# design.net
KiCad netlist of a schematic drawn in Altium Designer
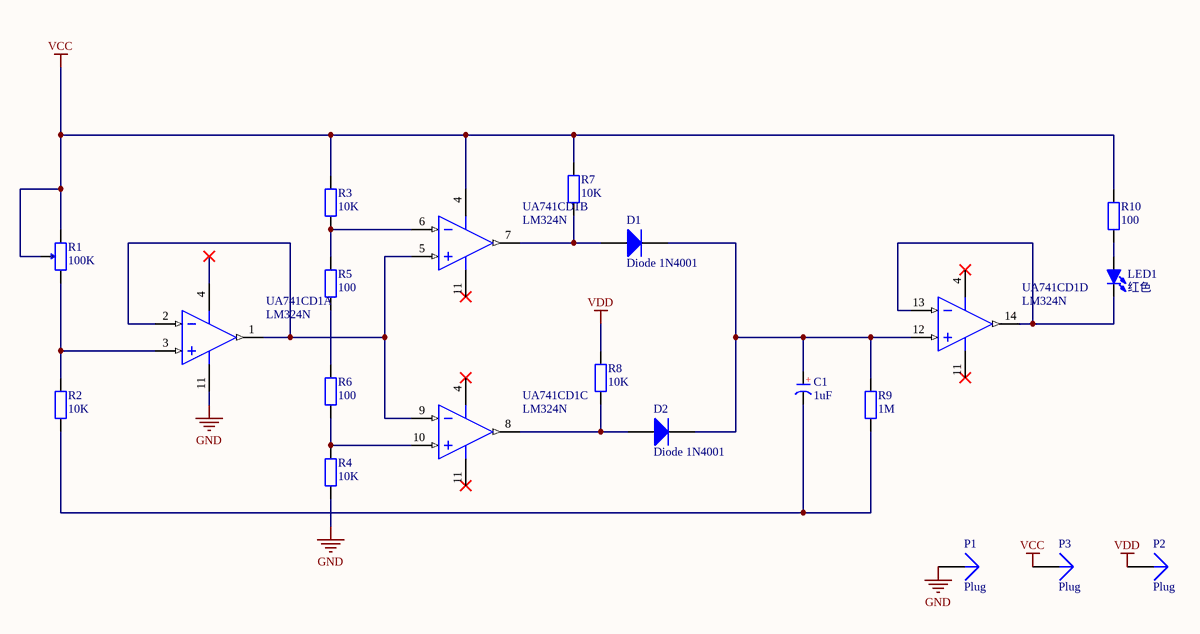
[diagram p0: 模电.SchDoc]

(export (version "E")
  (design (tool "Eeschema 10.0.6"))
  (components
    (comp (ref "C1")
      (value "1uF")
      (footprint "CAP 1.5*4*8")
      (description "直插电解电容")
      (libsource (lib "0.1 - 电阻-电容-电感") (part "C-CAP"))
    )
    (comp (ref "D1")
      (value "Diode 1N4001")
      (footprint "DO-41")
      (description "1 Amp General Purpose Rectifier")
      (fields (field (name "PUBLISHER") "Altium Limited"))
      (libsource (lib "Miscellaneous Devices") (part "Diode 1N4001"))
    )
    (comp (ref "D2")
      (value "Diode 1N4001")
      (footprint "DO-41")
      (description "1 Amp General Purpose Rectifier")
      (fields (field (name "PUBLISHER") "Altium Limited"))
      (libsource (lib "Miscellaneous Devices") (part "Diode 1N4001"))
    )
    (comp (ref "LED1")
      (value "红色")
      (footprint "LED 3MM-B")
      (description "插件LED")
      (libsource (lib "0.3 - LED") (part "LED-3MM"))
    )
    (comp (ref "P1")
      (value "Plug")
      (footprint "PIN1")
      (fields (field (name "PUBLISHER") "Altium Limited"))
      (libsource (lib "Miscellaneous Connectors") (part "Plug"))
    )
    (comp (ref "P2")
      (value "Plug")
      (footprint "PIN1")
      (fields (field (name "PUBLISHER") "Altium Limited"))
      (libsource (lib "Miscellaneous Connectors") (part "Plug"))
    )
    (comp (ref "P3")
      (value "Plug")
      (footprint "PIN1")
      (fields (field (name "PUBLISHER") "Altium Limited"))
      (libsource (lib "Miscellaneous Connectors") (part "Plug"))
    )
    (comp (ref "R1")
      (value "100K")
      (footprint "3362P")
      (description "贴片电位器")
      (libsource (lib "PCB_Project1") (part "RP-SMD"))
    )
    (comp (ref "R2")
      (value "10K")
      (footprint "RS 1/4W")
      (description "直插色环电阻")
      (libsource (lib "PCB_Project1") (part "R-CRR"))
    )
    (comp (ref "R3")
      (value "10K")
      (footprint "RS 1/4W")
      (description "直插色环电阻")
      (libsource (lib "PCB_Project1") (part "R-CRR"))
    )
    (comp (ref "R4")
      (value "10K")
      (footprint "RS 1/4W")
      (description "直插色环电阻")
      (libsource (lib "PCB_Project1") (part "R-CRR"))
    )
    (comp (ref "R5")
      (value "100")
      (footprint "RS 1/4W")
      (description "直插色环电阻")
      (libsource (lib "PCB_Project1") (part "R-CRR"))
    )
    (comp (ref "R6")
      (value "100")
      (footprint "RS 1/4W")
      (description "直插色环电阻")
      (libsource (lib "PCB_Project1") (part "R-CRR"))
    )
    (comp (ref "R7")
      (value "10K")
      (footprint "RS 1/4W")
      (description "直插色环电阻")
      (libsource (lib "PCB_Project1") (part "R-CRR"))
    )
    (comp (ref "R8")
      (value "10K")
      (footprint "RS 1/4W")
      (description "直插色环电阻")
      (libsource (lib "PCB_Project1") (part "R-CRR"))
    )
    (comp (ref "R9")
      (value "1M")
      (footprint "RS 1/4W")
      (description "直插色环电阻")
      (libsource (lib "PCB_Project1") (part "R-CRR"))
    )
    (comp (ref "R10")
      (value "100")
      (footprint "RS 1/4W")
      (description "直插色环电阻")
      (libsource (lib "PCB_Project1") (part "R-CRR"))
    )
    (comp (ref "UA741CD1")
      (value "LM324N")
      (footprint "DIP14")
      (description "Low Power Quad Operational Amplifier, 14-pin MDIP")
      (fields
        (field (name "MANUFACTURER") "National Semiconductor")
        (field (name "PUBLISHER") "Altium Limited")
      )
      (libsource (lib "Sheet1") (part "LM324N"))
    )
  )
  (nets
    (net (code "1") (name "GND") (class "Default")
      (node (ref "P1") (pin "1") (pinfunction "1_1") (pintype "passive"))
      (node (ref "R4") (pin "1") (pinfunction "1_1") (pintype "passive"))
      (node (ref "UA741CD1") (pin "11") (pinfunction "GND_11") (pintype "power_in"))
    )
    (net (code "2") (name "Net-(C1-A)") (class "Default")
      (node (ref "C1") (pin "1") (pinfunction "A_1") (pintype "passive"))
      (node (ref "D1") (pin "2") (pinfunction "K_2") (pintype "passive"))
      (node (ref "D2") (pin "2") (pinfunction "K_2") (pintype "passive"))
      (node (ref "R9") (pin "2") (pinfunction "2_2") (pintype "passive"))
      (node (ref "UA741CD1") (pin "12") (pinfunction "IN4+_12") (pintype "input"))
    )
    (net (code "3") (name "Net-(C1-K)") (class "Default")
      (node (ref "C1") (pin "2") (pinfunction "K_2") (pintype "passive"))
      (node (ref "R2") (pin "1") (pinfunction "1_1") (pintype "passive"))
      (node (ref "R9") (pin "1") (pinfunction "1_1") (pintype "passive"))
    )
    (net (code "4") (name "Net-(D1-A)") (class "Default")
      (node (ref "D1") (pin "1") (pinfunction "A_1") (pintype "passive"))
      (node (ref "R7") (pin "1") (pinfunction "1_1") (pintype "passive"))
      (node (ref "UA741CD1") (pin "7") (pinfunction "OUT2_7") (pintype "output"))
    )
    (net (code "5") (name "Net-(D2-A)") (class "Default")
      (node (ref "D2") (pin "1") (pinfunction "A_1") (pintype "passive"))
      (node (ref "R8") (pin "1") (pinfunction "1_1") (pintype "passive"))
      (node (ref "UA741CD1") (pin "8") (pinfunction "OUT3_8") (pintype "output"))
    )
    (net (code "6") (name "Net-(LED1-A)") (class "Default")
      (node (ref "LED1") (pin "1") (pinfunction "A_1") (pintype "passive"))
      (node (ref "R10") (pin "1") (pinfunction "1_1") (pintype "passive"))
    )
    (net (code "7") (name "Net-(LED1-K)") (class "Default")
      (node (ref "LED1") (pin "2") (pinfunction "K_2") (pintype "passive"))
      (node (ref "UA741CD1") (pin "13") (pinfunction "IN4-_13") (pintype "input"))
      (node (ref "UA741CD1") (pin "14") (pinfunction "OUT4_14") (pintype "output"))
    )
    (net (code "8") (name "Net-(R5-Pad1)") (class "Default")
      (node (ref "R5") (pin "1") (pinfunction "1_1") (pintype "passive"))
      (node (ref "R6") (pin "2") (pinfunction "2_2") (pintype "passive"))
    )
    (net (code "9") (name "Net-(UA741CD1A-IN1+)") (class "Default")
      (node (ref "R1") (pin "1") (pinfunction "1_1") (pintype "passive"))
      (node (ref "R2") (pin "2") (pinfunction "2_2") (pintype "passive"))
      (node (ref "UA741CD1") (pin "3") (pinfunction "IN1+_3") (pintype "input"))
    )
    (net (code "10") (name "Net-(UA741CD1A-IN1-)") (class "Default")
      (node (ref "UA741CD1") (pin "1") (pinfunction "OUT1_1") (pintype "output"))
      (node (ref "UA741CD1") (pin "2") (pinfunction "IN1-_2") (pintype "input"))
      (node (ref "UA741CD1") (pin "5") (pinfunction "IN2+_5") (pintype "input"))
      (node (ref "UA741CD1") (pin "9") (pinfunction "IN3-_9") (pintype "input"))
    )
    (net (code "11") (name "Net-(UA741CD1B-IN2-)") (class "Default")
      (node (ref "R3") (pin "1") (pinfunction "1_1") (pintype "passive"))
      (node (ref "R5") (pin "2") (pinfunction "2_2") (pintype "passive"))
      (node (ref "UA741CD1") (pin "6") (pinfunction "IN2-_6") (pintype "input"))
    )
    (net (code "12") (name "Net-(UA741CD1C-IN3+)") (class "Default")
      (node (ref "R4") (pin "2") (pinfunction "2_2") (pintype "passive"))
      (node (ref "R6") (pin "1") (pinfunction "1_1") (pintype "passive"))
      (node (ref "UA741CD1") (pin "10") (pinfunction "IN3+_10") (pintype "input"))
    )
    (net (code "13") (name "VCC") (class "Default")
      (node (ref "P3") (pin "1") (pinfunction "1_1") (pintype "passive"))
      (node (ref "R1") (pin "2") (pinfunction "2_2") (pintype "passive"))
      (node (ref "R1") (pin "3") (pinfunction "3_3") (pintype "passive"))
      (node (ref "R10") (pin "2") (pinfunction "2_2") (pintype "passive"))
      (node (ref "R3") (pin "2") (pinfunction "2_2") (pintype "passive"))
      (node (ref "R7") (pin "2") (pinfunction "2_2") (pintype "passive"))
      (node (ref "UA741CD1") (pin "4") (pinfunction "V+_4") (pintype "power_in"))
    )
    (net (code "14") (name "VDD") (class "Default")
      (node (ref "P2") (pin "1") (pinfunction "1_1") (pintype "passive"))
      (node (ref "R8") (pin "2") (pinfunction "2_2") (pintype "passive"))
    )
    (net (code "15") (name "unconnected-(UA741CD1A-V+-Pad4)") (class "Default")
      (node (ref "UA741CD1") (pin "4") (pinfunction "V+_4") (pintype "power_in+no_connect"))
    )
    (net (code "16") (name "unconnected-(UA741CD1B-GND-Pad11)") (class "Default")
      (node (ref "UA741CD1") (pin "11") (pinfunction "GND_11") (pintype "power_in+no_connect"))
    )
    (net (code "17") (name "unconnected-(UA741CD1C-GND-Pad11)") (class "Default")
      (node (ref "UA741CD1") (pin "11") (pinfunction "GND_11") (pintype "power_in+no_connect"))
    )
    (net (code "18") (name "unconnected-(UA741CD1C-V+-Pad4)") (class "Default")
      (node (ref "UA741CD1") (pin "4") (pinfunction "V+_4") (pintype "power_in+no_connect"))
    )
    (net (code "19") (name "unconnected-(UA741CD1D-GND-Pad11)") (class "Default")
      (node (ref "UA741CD1") (pin "11") (pinfunction "GND_11") (pintype "power_in+no_connect"))
    )
    (net (code "20") (name "unconnected-(UA741CD1D-V+-Pad4)") (class "Default")
      (node (ref "UA741CD1") (pin "4") (pinfunction "V+_4") (pintype "power_in+no_connect"))
    )
  )
)
